# HMC472_SPF5189.net
KiCad netlist of a schematic drawn in Altium Designer
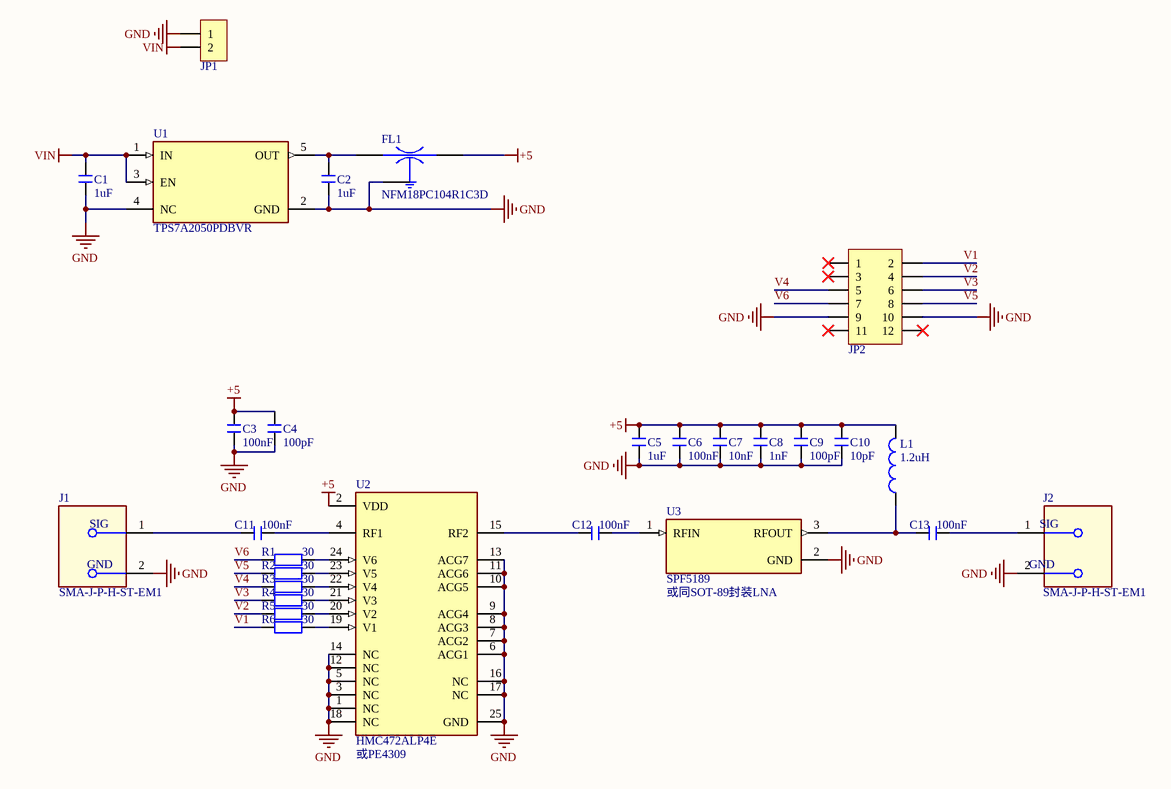
[diagram p0: HMC472_SPF5189.SchDoc]

(export (version "E")
  (design (tool "Eeschema 10.0.6"))
  (components
    (comp (ref "C1")
      (value "1uF")
      (footprint "C 0603_L")
      (description "贴片电容")
      (libsource (lib "01 - 电容-电阻-电感") (part "C"))
    )
    (comp (ref "C2")
      (value "1uF")
      (footprint "C 0603_L")
      (description "贴片电容")
      (libsource (lib "01 - 电容-电阻-电感") (part "C"))
    )
    (comp (ref "C3")
      (value "100nF")
      (footprint "C 0603_L")
      (description "贴片电容")
      (libsource (lib "01 - 电容-电阻-电感") (part "C"))
    )
    (comp (ref "C4")
      (value "100pF")
      (footprint "C 0603_L")
      (description "贴片电容")
      (libsource (lib "01 - 电容-电阻-电感") (part "C"))
    )
    (comp (ref "C5")
      (value "1uF")
      (footprint "C 0603_L")
      (description "贴片电容")
      (libsource (lib "01 - 电容-电阻-电感") (part "C"))
    )
    (comp (ref "C6")
      (value "100nF")
      (footprint "C 0603_L")
      (description "贴片电容")
      (libsource (lib "01 - 电容-电阻-电感") (part "C"))
    )
    (comp (ref "C7")
      (value "10nF")
      (footprint "C 0603_L")
      (description "贴片电容")
      (libsource (lib "01 - 电容-电阻-电感") (part "C"))
    )
    (comp (ref "C8")
      (value "1nF")
      (footprint "C 0603_L")
      (description "贴片电容")
      (libsource (lib "01 - 电容-电阻-电感") (part "C"))
    )
    (comp (ref "C9")
      (value "100pF")
      (footprint "C 0603_L")
      (description "贴片电容")
      (libsource (lib "01 - 电容-电阻-电感") (part "C"))
    )
    (comp (ref "C10")
      (value "10pF")
      (footprint "C 0603_L")
      (description "贴片电容")
      (libsource (lib "01 - 电容-电阻-电感") (part "C"))
    )
    (comp (ref "C11")
      (value "100nF")
      (footprint "C 0603_L")
      (description "贴片电容")
      (libsource (lib "01 - 电容-电阻-电感") (part "C"))
    )
    (comp (ref "C12")
      (value "100nF")
      (footprint "C 0603_L")
      (description "贴片电容")
      (libsource (lib "01 - 电容-电阻-电感") (part "C"))
    )
    (comp (ref "C13")
      (value "100nF")
      (footprint "C 0603_L")
      (description "贴片电容")
      (libsource (lib "01 - 电容-电阻-电感") (part "C"))
    )
    (comp (ref "FL1")
      (value "NFM18PC104R1C3D")
      (footprint "FIL_NFM18PC104R1C3D")
      (description "SMD Capacitor with Capacitance: 0.10uF Tol. 20%. Rated Voltage: 16Vdc")
      (fields (field (name "MF") "Murata") (field (name "DIGI-KEY_PART_NUMBER") "490-6969-1-ND"))
      (libsource (lib "NFM18PC104R1C3D") (part "NFM18PC104R1C3D"))
    )
    (comp (ref "J1")
      (value "SMA-J-P-H-ST-EM1")
      (footprint "FP-SMA-J-P-H-ST-EM1-MFG")
      (description "CONN SMA JACK STR 50OHM EDGE MNT")
      (libsource (lib "") (part "CMP-02754-000006-1_1"))
    )
    (comp (ref "J2")
      (value "SMA-J-P-H-ST-EM1")
      (footprint "FP-SMA-J-P-H-ST-EM1-MFG")
      (description "CONN SMA JACK STR 50OHM EDGE MNT")
      (libsource (lib "卧式SMA") (part "CMP-02754-000006-1"))
    )
    (comp (ref "JP1")
      (value "HDR-1X2")
      (footprint "KF2510-LI-2P")
      (description "2P接插件")
      (libsource (lib "18 - 接插件-脚距2.54mm (100mil) ") (part "Header 2"))
    )
    (comp (ref "JP2")
      (value "Header 6X2")
      (footprint "HDR2.54-WI-2x6P")
      (description "6*2P接插件")
      (libsource (lib "18 - 接插件-脚距2.54mm (100mil) ") (part "Header  6X2"))
    )
    (comp (ref "L1")
      (value "1.2uH")
      (footprint "IND-SMD_L2.9-W2.8")
      (description "小功率贴片电感")
      (libsource (lib "01 - 电容-电阻-电感") (part "L"))
    )
    (comp (ref "R1")
      (value "30")
      (footprint "R 0402_L")
      (description "贴片电阻")
      (libsource (lib "01 - 电容-电阻-电感") (part "R"))
    )
    (comp (ref "R2")
      (value "30")
      (footprint "R 0402_L")
      (description "贴片电阻")
      (libsource (lib "01 - 电容-电阻-电感") (part "R"))
    )
    (comp (ref "R3")
      (value "30")
      (footprint "R 0402_L")
      (description "贴片电阻")
      (libsource (lib "01 - 电容-电阻-电感") (part "R"))
    )
    (comp (ref "R4")
      (value "30")
      (footprint "R 0402_L")
      (description "贴片电阻")
      (libsource (lib "01 - 电容-电阻-电感") (part "R"))
    )
    (comp (ref "R5")
      (value "30")
      (footprint "R 0402_L")
      (description "贴片电阻")
      (libsource (lib "01 - 电容-电阻-电感") (part "R"))
    )
    (comp (ref "R6")
      (value "30")
      (footprint "R 0402_L")
      (description "贴片电阻")
      (libsource (lib "01 - 电容-电阻-电感") (part "R"))
    )
    (comp (ref "U1")
      (value "TPS7A2050PDBVR")
      (footprint "FP-DBV0005A-IPC_C")
      (libsource (lib "TPS7A2050DBVR") (part "TPS7A2050"))
    )
    (comp (ref "U2")
      (value "HMC472ALP4E")
      (footprint "FP-HMC472ALP4E-IPC_A")
      (description "RF ATTENUATOR 31.5DB 50OHM 24QFN")
      (fields
        (field (name "OCTOPART") "https://octopart.com/hmc472alp4e-analog+devices-51966954")
        (field (name "MANUFACTURER") "Analog Devices")
      )
      (libsource (lib "HMC472ALP4E") (part "HMC472ALP4E"))
    )
    (comp (ref "U3")
      (value "SPF5189")
      (footprint "FP-RK-3-MFG")
      (description "IC RF AMP GP 0HZ-5GHZ SOT89")
      (libsource (lib "HMC480") (part "HMC480"))
    )
  )
  (nets
    (net (code "1") (name "+5") (class "Default")
      (node (ref "C10") (pin "2") (pinfunction "2_2") (pintype "passive"))
      (node (ref "C3") (pin "2") (pinfunction "2_2") (pintype "passive"))
      (node (ref "C4") (pin "2") (pinfunction "2_2") (pintype "passive"))
      (node (ref "C5") (pin "2") (pinfunction "2_2") (pintype "passive"))
      (node (ref "C6") (pin "2") (pinfunction "2_2") (pintype "passive"))
      (node (ref "C7") (pin "2") (pinfunction "2_2") (pintype "passive"))
      (node (ref "C8") (pin "2") (pinfunction "2_2") (pintype "passive"))
      (node (ref "C9") (pin "2") (pinfunction "2_2") (pintype "passive"))
      (node (ref "FL1") (pin "3") (pinfunction "OUT_3") (pintype "passive"))
      (node (ref "L1") (pin "2") (pinfunction "2_2") (pintype "passive"))
      (node (ref "U2") (pin "2") (pinfunction "VDD_2") (pintype "power_in"))
    )
    (net (code "2") (name "/V1") (class "Default")
      (node (ref "JP2") (pin "2") (pinfunction "2_2") (pintype "passive"))
      (node (ref "R6") (pin "1") (pinfunction "1_1") (pintype "passive"))
    )
    (net (code "3") (name "/V2") (class "Default")
      (node (ref "JP2") (pin "4") (pinfunction "4_4") (pintype "passive"))
      (node (ref "R5") (pin "1") (pinfunction "1_1") (pintype "passive"))
    )
    (net (code "4") (name "/V3") (class "Default")
      (node (ref "JP2") (pin "6") (pinfunction "6_6") (pintype "passive"))
      (node (ref "R4") (pin "1") (pinfunction "1_1") (pintype "passive"))
    )
    (net (code "5") (name "/V4") (class "Default")
      (node (ref "JP2") (pin "5") (pinfunction "5_5") (pintype "passive"))
      (node (ref "R3") (pin "1") (pinfunction "1_1") (pintype "passive"))
    )
    (net (code "6") (name "/V5") (class "Default")
      (node (ref "JP2") (pin "8") (pinfunction "8_8") (pintype "passive"))
      (node (ref "R2") (pin "1") (pinfunction "1_1") (pintype "passive"))
    )
    (net (code "7") (name "/V6") (class "Default")
      (node (ref "JP2") (pin "7") (pinfunction "7_7") (pintype "passive"))
      (node (ref "R1") (pin "1") (pinfunction "1_1") (pintype "passive"))
    )
    (net (code "8") (name "GND") (class "Default")
      (node (ref "C1") (pin "1") (pinfunction "1_1") (pintype "passive"))
      (node (ref "C10") (pin "1") (pinfunction "1_1") (pintype "passive"))
      (node (ref "C2") (pin "1") (pinfunction "1_1") (pintype "passive"))
      (node (ref "C3") (pin "1") (pinfunction "1_1") (pintype "passive"))
      (node (ref "C4") (pin "1") (pinfunction "1_1") (pintype "passive"))
      (node (ref "C5") (pin "1") (pinfunction "1_1") (pintype "passive"))
      (node (ref "C6") (pin "1") (pinfunction "1_1") (pintype "passive"))
      (node (ref "C7") (pin "1") (pinfunction "1_1") (pintype "passive"))
      (node (ref "C8") (pin "1") (pinfunction "1_1") (pintype "passive"))
      (node (ref "C9") (pin "1") (pinfunction "1_1") (pintype "passive"))
      (node (ref "FL1") (pin "2") (pinfunction "GND_2") (pintype "power_in"))
      (node (ref "J1") (pin "2") (pinfunction "MNT_1_2") (pintype "passive"))
      (node (ref "J2") (pin "2") (pinfunction "MNT_1_2") (pintype "passive"))
      (node (ref "JP1") (pin "1") (pinfunction "1_1") (pintype "passive"))
      (node (ref "JP2") (pin "10") (pinfunction "10_10") (pintype "passive"))
      (node (ref "JP2") (pin "9") (pinfunction "9_9") (pintype "passive"))
      (node (ref "U1") (pin "2") (pinfunction "GND_2") (pintype "power_in"))
      (node (ref "U1") (pin "4") (pinfunction "NC_4") (pintype "passive"))
      (node (ref "U2") (pin "1") (pinfunction "NC_1") (pintype "passive"))
      (node (ref "U2") (pin "10") (pinfunction "ACG5_10") (pintype "passive"))
      (node (ref "U2") (pin "11") (pinfunction "ACG6_11") (pintype "passive"))
      (node (ref "U2") (pin "12") (pinfunction "NC_12") (pintype "passive"))
      (node (ref "U2") (pin "13") (pinfunction "ACG7_13") (pintype "passive"))
      (node (ref "U2") (pin "14") (pinfunction "NC_14") (pintype "passive"))
      (node (ref "U2") (pin "16") (pinfunction "NC_16") (pintype "passive"))
      (node (ref "U2") (pin "17") (pinfunction "NC_17") (pintype "passive"))
      (node (ref "U2") (pin "18") (pinfunction "NC_18") (pintype "passive"))
      (node (ref "U2") (pin "25") (pinfunction "GND_25") (pintype "power_in"))
      (node (ref "U2") (pin "3") (pinfunction "NC_3") (pintype "passive"))
      (node (ref "U2") (pin "5") (pinfunction "NC_5") (pintype "passive"))
      (node (ref "U2") (pin "6") (pinfunction "ACG1_6") (pintype "passive"))
      (node (ref "U2") (pin "7") (pinfunction "ACG2_7") (pintype "passive"))
      (node (ref "U2") (pin "8") (pinfunction "ACG3_8") (pintype "passive"))
      (node (ref "U2") (pin "9") (pinfunction "ACG4_9") (pintype "passive"))
      (node (ref "U3") (pin "2") (pinfunction "GND_2") (pintype "power_in"))
    )
    (net (code "9") (name "Net-(C11-Pad1)") (class "Default")
      (node (ref "C11") (pin "1") (pinfunction "1_1") (pintype "passive"))
      (node (ref "J1") (pin "1") (pinfunction "1_1") (pintype "passive"))
    )
    (net (code "10") (name "Net-(C13-Pad2)") (class "Default")
      (node (ref "C13") (pin "2") (pinfunction "2_2") (pintype "passive"))
      (node (ref "J2") (pin "1") (pinfunction "1_1") (pintype "passive"))
    )
    (net (code "11") (name "Net-(FL1-IN)") (class "Default")
      (node (ref "C2") (pin "2") (pinfunction "2_2") (pintype "passive"))
      (node (ref "FL1") (pin "1") (pinfunction "IN_1") (pintype "passive"))
      (node (ref "U1") (pin "5") (pinfunction "OUT_5") (pintype "output"))
    )
    (net (code "12") (name "Net-(U2-RF1)") (class "Default")
      (node (ref "C11") (pin "2") (pinfunction "2_2") (pintype "passive"))
      (node (ref "U2") (pin "4") (pinfunction "RF1_4") (pintype "passive"))
    )
    (net (code "13") (name "Net-(U2-RF2)") (class "Default")
      (node (ref "C12") (pin "1") (pinfunction "1_1") (pintype "passive"))
      (node (ref "U2") (pin "15") (pinfunction "RF2_15") (pintype "passive"))
    )
    (net (code "14") (name "Net-(U2-V1)") (class "Default")
      (node (ref "R6") (pin "2") (pinfunction "2_2") (pintype "passive"))
      (node (ref "U2") (pin "19") (pinfunction "V1_19") (pintype "input"))
    )
    (net (code "15") (name "Net-(U2-V2)") (class "Default")
      (node (ref "R5") (pin "2") (pinfunction "2_2") (pintype "passive"))
      (node (ref "U2") (pin "20") (pinfunction "V2_20") (pintype "input"))
    )
    (net (code "16") (name "Net-(U2-V3)") (class "Default")
      (node (ref "R4") (pin "2") (pinfunction "2_2") (pintype "passive"))
      (node (ref "U2") (pin "21") (pinfunction "V3_21") (pintype "input"))
    )
    (net (code "17") (name "Net-(U2-V4)") (class "Default")
      (node (ref "R3") (pin "2") (pinfunction "2_2") (pintype "passive"))
      (node (ref "U2") (pin "22") (pinfunction "V4_22") (pintype "input"))
    )
    (net (code "18") (name "Net-(U2-V5)") (class "Default")
      (node (ref "R2") (pin "2") (pinfunction "2_2") (pintype "passive"))
      (node (ref "U2") (pin "23") (pinfunction "V5_23") (pintype "input"))
    )
    (net (code "19") (name "Net-(U2-V6)") (class "Default")
      (node (ref "R1") (pin "2") (pinfunction "2_2") (pintype "passive"))
      (node (ref "U2") (pin "24") (pinfunction "V6_24") (pintype "input"))
    )
    (net (code "20") (name "Net-(U3-RFIN)") (class "Default")
      (node (ref "C12") (pin "2") (pinfunction "2_2") (pintype "passive"))
      (node (ref "U3") (pin "1") (pinfunction "RFIN_1") (pintype "input"))
    )
    (net (code "21") (name "Net-(U3-RFOUT)") (class "Default")
      (node (ref "C13") (pin "1") (pinfunction "1_1") (pintype "passive"))
      (node (ref "L1") (pin "1") (pinfunction "1_1") (pintype "passive"))
      (node (ref "U3") (pin "3") (pinfunction "RFOUT_3") (pintype "output"))
    )
    (net (code "22") (name "VIN") (class "Default")
      (node (ref "C1") (pin "2") (pinfunction "2_2") (pintype "passive"))
      (node (ref "JP1") (pin "2") (pinfunction "2_2") (pintype "passive"))
      (node (ref "U1") (pin "1") (pinfunction "IN_1") (pintype "input"))
      (node (ref "U1") (pin "3") (pinfunction "EN_3") (pintype "input"))
    )
    (net (code "23") (name "unconnected-(JP2-Pad1)") (class "Default")
      (node (ref "JP2") (pin "1") (pinfunction "1_1") (pintype "passive+no_connect"))
    )
    (net (code "24") (name "unconnected-(JP2-Pad3)") (class "Default")
      (node (ref "JP2") (pin "3") (pinfunction "3_3") (pintype "passive+no_connect"))
    )
    (net (code "25") (name "unconnected-(JP2-Pad11)") (class "Default")
      (node (ref "JP2") (pin "11") (pinfunction "11_11") (pintype "passive+no_connect"))
    )
    (net (code "26") (name "unconnected-(JP2-Pad12)") (class "Default")
      (node (ref "JP2") (pin "12") (pinfunction "12_12") (pintype "passive+no_connect"))
    )
  )
)
